# dac_audio_out.net
KiCad netlist of a schematic drawn in Altium Designer
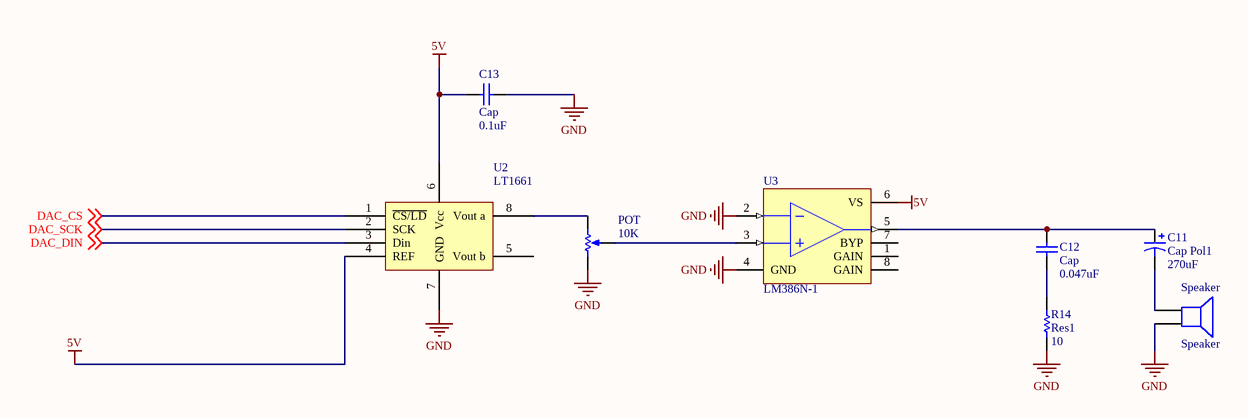
[diagram p0: dac_audio_out.SchDoc]

(export (version "E")
  (design (tool "Eeschema 10.0.6"))
  (components
    (comp (ref "C11")
      (value "Cap Pol1")
      (footprint "AXIAL-0.3")
      (description "Polarized Capacitor (Radial)")
      (fields (field (name "ALTIUM_VALUE") "270uF") (field (name "PUBLISHER") "Altium Limited"))
      (libsource (lib "Miscellaneous Devices") (part "Cap Pol1"))
    )
    (comp (ref "C12")
      (value "Cap")
      (footprint "6-0805_M")
      (description "Capacitor")
      (fields (field (name "ALTIUM_VALUE") "0.047uF") (field (name "PUBLISHER") "Altium Limited"))
      (libsource (lib "Miscellaneous Devices") (part "Cap"))
    )
    (comp (ref "C13")
      (value "Cap")
      (footprint "6-0805_M")
      (description "Capacitor")
      (fields (field (name "ALTIUM_VALUE") "0.1uF") (field (name "PUBLISHER") "Altium Limited"))
      (libsource (lib "Miscellaneous Devices") (part "Cap"))
    )
    (comp (ref "POT")
      (value "10K")
      (footprint "VR5")
      (description "Potentiometer")
      (fields (field (name "Comment") "RPot_3") (field (name "PUBLISHER") "Altium Limited"))
      (libsource (lib "ECE LIB new") (part "RPot"))
    )
    (comp (ref "R14")
      (value "Res1")
      (footprint "6-0805_M")
      (description "Resistor")
      (fields (field (name "ALTIUM_VALUE") "10") (field (name "PUBLISHER") "Altium Limited"))
      (libsource (lib "Miscellaneous Devices") (part "Res1"))
    )
    (comp (ref "Speaker")
      (value "Speaker")
      (footprint "PIN2")
      (description "Loudspeaker")
      (fields (field (name "PUBLISHER") "Altium Limited"))
      (libsource (lib "Miscellaneous Devices") (part "Speaker"))
    )
    (comp (ref "U2") (value "LT1661") (footprint "DIP-8") (libsource (lib "ECE LIB new") (part "LT1661")))
    (comp (ref "U3")
      (value "LM386N-1")
      (footprint "DIP-8")
      (description "Low-Voltage Audio Power Amplifier")
      (fields (field (name "PUBLISHER") "Altium Limited"))
      (libsource (lib "ECE LIB new") (part "LM386N-1"))
    )
  )
  (nets
    (net (code "1") (name "5V") (class "Default")
      (node (ref "C13") (pin "1") (pinfunction "1_1") (pintype "passive"))
      (node (ref "U2") (pin "4") (pinfunction "REF_4") (pintype "passive"))
      (node (ref "U2") (pin "6") (pinfunction "Vcc_6") (pintype "passive"))
      (node (ref "U3") (pin "6") (pinfunction "VS_6") (pintype "power_in"))
    )
    (net (code "2") (name "DAC_CS") (class "Default")
      (node (ref "U2") (pin "1") (pinfunction "~{CS/LD}_1") (pintype "passive"))
    )
    (net (code "3") (name "DAC_DIN") (class "Default")
      (node (ref "U2") (pin "3") (pinfunction "Din_3") (pintype "passive"))
    )
    (net (code "4") (name "DAC_SCK") (class "Default")
      (node (ref "U2") (pin "2") (pinfunction "SCK_2") (pintype "passive"))
    )
    (net (code "5") (name "GND") (class "Default")
      (node (ref "C13") (pin "2") (pinfunction "2_2") (pintype "passive"))
      (node (ref "POT") (pin "1") (pinfunction "TOP_1") (pintype "passive"))
      (node (ref "R14") (pin "1") (pinfunction "1_1") (pintype "passive"))
      (node (ref "Speaker") (pin "2") (pinfunction "2_2") (pintype "passive"))
      (node (ref "U2") (pin "7") (pinfunction "GND_7") (pintype "passive"))
      (node (ref "U3") (pin "2") (pinfunction "IN-_2") (pintype "input"))
      (node (ref "U3") (pin "4") (pinfunction "GND_4") (pintype "power_in"))
    )
    (net (code "6") (name "Net-(C11-Pad2)") (class "Default")
      (node (ref "C11") (pin "2") (pinfunction "2_2") (pintype "passive"))
      (node (ref "Speaker") (pin "1") (pinfunction "1_1") (pintype "passive"))
    )
    (net (code "7") (name "Net-(C12-Pad1)") (class "Default")
      (node (ref "C12") (pin "1") (pinfunction "1_1") (pintype "passive"))
      (node (ref "R14") (pin "2") (pinfunction "2_2") (pintype "passive"))
    )
    (net (code "8") (name "Net-(POT-BOT)") (class "Default")
      (node (ref "POT") (pin "3") (pinfunction "BOT_3") (pintype "passive"))
      (node (ref "U2") (pin "8") (pinfunction "Vout_a_8") (pintype "passive"))
    )
    (net (code "9") (name "Net-(POT-TAP)") (class "Default")
      (node (ref "POT") (pin "2") (pinfunction "TAP_2") (pintype "passive"))
      (node (ref "U3") (pin "3") (pinfunction "IN+_3") (pintype "input"))
    )
    (net (code "10") (name "Net-(U3-OUT)") (class "Default")
      (node (ref "C11") (pin "1") (pinfunction "1_1") (pintype "passive"))
      (node (ref "C12") (pin "2") (pinfunction "2_2") (pintype "passive"))
      (node (ref "U3") (pin "5") (pinfunction "OUT_5") (pintype "output"))
    )
    (net (code "11") (name "unconnected-(U2-Vout_b-Pad5)") (class "Default")
      (node (ref "U2") (pin "5") (pinfunction "Vout_b_5") (pintype "passive"))
    )
    (net (code "12") (name "unconnected-(U3-BYP-Pad7)") (class "Default")
      (node (ref "U3") (pin "7") (pinfunction "BYP_7") (pintype "passive"))
    )
    (net (code "13") (name "unconnected-(U3-GAIN-Pad1)") (class "Default")
      (node (ref "U3") (pin "1") (pinfunction "GAIN_1") (pintype "passive"))
    )
    (net (code "14") (name "unconnected-(U3-GAIN-Pad8)") (class "Default")
      (node (ref "U3") (pin "8") (pinfunction "GAIN_8") (pintype "passive"))
    )
  )
)
